# FINGER_USB_HUB.net
KiCad netlist of a schematic drawn in Altium Designer
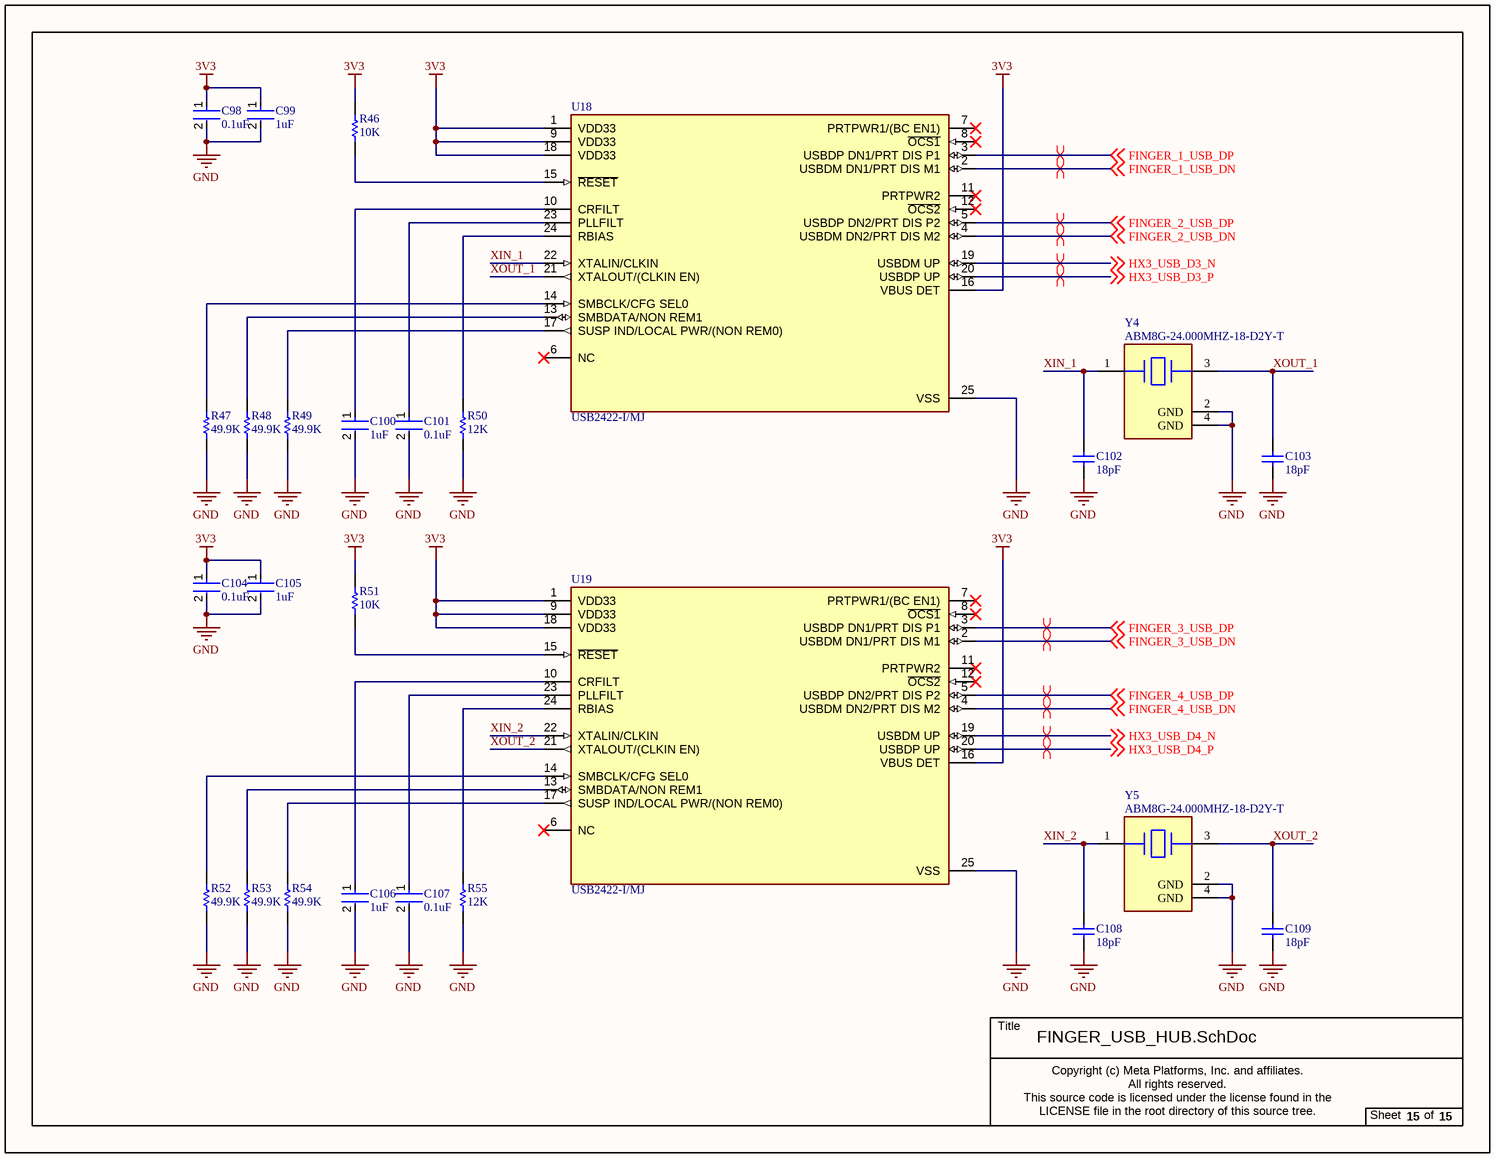
[diagram p0: FINGER_USB_HUB.SchDoc]

(export (version "E")
  (design (tool "Eeschema 10.0.6"))
  (components
    (comp (ref "C98")
      (value "0.1uF")
      (footprint "FP-CC0201-BA-MFG")
      (description "CAP CER 0.1UF 6.3V X5R 0201")
      (fields (field (name "MANUFACTURER") "Yageo") (field (name "TOLERANCE") "0.1"))
      (libsource (lib "Altium Content Vault") (part "11868f565c42a9108669ba33697ecf6"))
    )
    (comp (ref "C99")
      (value "1uF")
      (footprint "FP-CL511-IPC_C")
      (description "Cap Ceramic 1uF 10V X5R ±10% SMD 0402 +85°C Paper T/R")
      (fields (field (name "TOLERANCE") "10%"))
      (libsource (lib "Altium Content Vault") (part "b4654b650e69147ec39a6b967a45e02"))
    )
    (comp (ref "C100")
      (value "1uF")
      (footprint "FP-CL511-IPC_C")
      (description "Cap Ceramic 1uF 10V X5R ±10% SMD 0402 +85°C Paper T/R")
      (fields (field (name "TOLERANCE") "10%"))
      (libsource (lib "Altium Content Vault") (part "b4654b650e69147ec39a6b967a45e02"))
    )
    (comp (ref "C101")
      (value "0.1uF")
      (footprint "FP-CC0201-BA-MFG")
      (description "CAP CER 0.1UF 6.3V X5R 0201")
      (fields (field (name "MANUFACTURER") "Yageo") (field (name "TOLERANCE") "0.1"))
      (libsource (lib "Altium Content Vault") (part "11868f565c42a9108669ba33697ecf6"))
    )
    (comp (ref "C102")
      (value "18pF")
      (footprint "CAPC1005X55X25NL05T10")
      (fields (field (name "PART NUMBER") "GRM1555C1H180JA01D") (field (name "MANUFACTURER") "Murata"))
      (libsource (lib "Altium Content Vault") (part "CAP"))
    )
    (comp (ref "C103")
      (value "18pF")
      (footprint "CAPC1005X55X25NL05T10")
      (fields (field (name "PART NUMBER") "GRM1555C1H180JA01D") (field (name "MANUFACTURER") "Murata"))
      (libsource (lib "Altium Content Vault") (part "CAP"))
    )
    (comp (ref "C104")
      (value "0.1uF")
      (footprint "FP-CC0201-BA-MFG")
      (description "CAP CER 0.1UF 6.3V X5R 0201")
      (fields (field (name "MANUFACTURER") "Yageo") (field (name "TOLERANCE") "0.1"))
      (libsource (lib "Altium Content Vault") (part "11868f565c42a9108669ba33697ecf6"))
    )
    (comp (ref "C105")
      (value "1uF")
      (footprint "FP-CL511-IPC_C")
      (description "Cap Ceramic 1uF 10V X5R ±10% SMD 0402 +85°C Paper T/R")
      (fields (field (name "TOLERANCE") "10%"))
      (libsource (lib "Altium Content Vault") (part "b4654b650e69147ec39a6b967a45e02"))
    )
    (comp (ref "C106")
      (value "1uF")
      (footprint "FP-CL511-IPC_C")
      (description "Cap Ceramic 1uF 10V X5R ±10% SMD 0402 +85°C Paper T/R")
      (fields (field (name "TOLERANCE") "10%"))
      (libsource (lib "Altium Content Vault") (part "b4654b650e69147ec39a6b967a45e02"))
    )
    (comp (ref "C107")
      (value "0.1uF")
      (footprint "FP-CC0201-BA-MFG")
      (description "CAP CER 0.1UF 6.3V X5R 0201")
      (fields (field (name "MANUFACTURER") "Yageo") (field (name "TOLERANCE") "0.1"))
      (libsource (lib "Altium Content Vault") (part "11868f565c42a9108669ba33697ecf6"))
    )
    (comp (ref "C108")
      (value "18pF")
      (footprint "CAPC1005X55X25NL05T10")
      (fields (field (name "PART NUMBER") "GRM1555C1H180JA01D") (field (name "MANUFACTURER") "Murata"))
      (libsource (lib "Altium Content Vault") (part "CAP"))
    )
    (comp (ref "C109")
      (value "18pF")
      (footprint "CAPC1005X55X25NL05T10")
      (fields (field (name "PART NUMBER") "GRM1555C1H180JA01D") (field (name "MANUFACTURER") "Murata"))
      (libsource (lib "Altium Content Vault") (part "CAP"))
    )
    (comp (ref "R46")
      (value "10K")
      (footprint "RESC1005X40X25ML05T10")
      (fields (field (name "PART NUMBER") "CRCW040210K0FKEDHP") (field (name "MANUFACTURER") "Vishay Dale"))
      (libsource (lib "Altium Content Vault") (part "RES"))
    )
    (comp (ref "R47")
      (value "49.9K")
      (footprint "RESC1005X40X25ML05T10")
      (fields (field (name "MANUFACTURER") "Yageo / Phycomp") (field (name "PART NUMBER") "RC0402FR-0749K9L"))
      (libsource (lib "Altium Content Vault") (part "RES"))
    )
    (comp (ref "R48")
      (value "49.9K")
      (footprint "RESC1005X40X25ML05T10")
      (fields (field (name "MANUFACTURER") "Yageo / Phycomp") (field (name "PART NUMBER") "RC0402FR-0749K9L"))
      (libsource (lib "Altium Content Vault") (part "RES"))
    )
    (comp (ref "R49")
      (value "49.9K")
      (footprint "RESC1005X40X25ML05T10")
      (fields (field (name "MANUFACTURER") "Yageo / Phycomp") (field (name "PART NUMBER") "RC0402FR-0749K9L"))
      (libsource (lib "Altium Content Vault") (part "RES"))
    )
    (comp (ref "R50")
      (value "12K")
      (footprint "RESC1005X40X25ML05T05")
      (description "Chip Resistor, 12 KOhm, +/- 1%, 0.1 W, -55 to 155 degC, 0402 (1005 Metric), RoHS, Tape and Reel")
      (fields (field (name "TOLERANCE") "1%") (field (name "PARTNUMBER") "ERJ-2RKF1202X"))
      (libsource (lib "Altium Content Vault") (part "RES-2"))
    )
    (comp (ref "R51")
      (value "10K")
      (footprint "RESC1005X40X25ML05T10")
      (fields (field (name "PART NUMBER") "CRCW040210K0FKEDHP") (field (name "MANUFACTURER") "Vishay Dale"))
      (libsource (lib "Altium Content Vault") (part "RES"))
    )
    (comp (ref "R52")
      (value "49.9K")
      (footprint "RESC1005X40X25ML05T10")
      (fields (field (name "MANUFACTURER") "Yageo / Phycomp") (field (name "PART NUMBER") "RC0402FR-0749K9L"))
      (libsource (lib "Altium Content Vault") (part "RES"))
    )
    (comp (ref "R53")
      (value "49.9K")
      (footprint "RESC1005X40X25ML05T10")
      (fields (field (name "MANUFACTURER") "Yageo / Phycomp") (field (name "PART NUMBER") "RC0402FR-0749K9L"))
      (libsource (lib "Altium Content Vault") (part "RES"))
    )
    (comp (ref "R54")
      (value "49.9K")
      (footprint "RESC1005X40X25ML05T10")
      (fields (field (name "MANUFACTURER") "Yageo / Phycomp") (field (name "PART NUMBER") "RC0402FR-0749K9L"))
      (libsource (lib "Altium Content Vault") (part "RES"))
    )
    (comp (ref "R55")
      (value "12K")
      (footprint "RESC1005X40X25ML05T05")
      (description "Chip Resistor, 12 KOhm, +/- 1%, 0.1 W, -55 to 155 degC, 0402 (1005 Metric), RoHS, Tape and Reel")
      (fields (field (name "TOLERANCE") "1%") (field (name "PARTNUMBER") "ERJ-2RKF1202X"))
      (libsource (lib "Altium Content Vault") (part "RES-2"))
    )
    (comp (ref "U18")
      (value "USB2422-I/MJ")
      (footprint "FP-24-S4QFN-4x4B-0_5P-MFG")
      (description "IC HUB CTLR USB 2.0 24QFN")
      (fields
        (field (name "MANUFACTURER") "Microchip")
        (field (name "OCTOPART") "https://octopart.com/usb2422-i%2Fmj-microchip-29030614")
      )
      (libsource (lib "Altium Content Vault") (part "e4aea346ed290c10a3dfb05f2f32753"))
    )
    (comp (ref "U19")
      (value "USB2422-I/MJ")
      (footprint "FP-24-S4QFN-4x4B-0_5P-MFG")
      (description "IC HUB CTLR USB 2.0 24QFN")
      (fields
        (field (name "MANUFACTURER") "Microchip")
        (field (name "OCTOPART") "https://octopart.com/usb2422-i%2Fmj-microchip-29030614")
      )
      (libsource (lib "Altium Content Vault") (part "e4aea346ed290c10a3dfb05f2f32753"))
    )
    (comp (ref "Y4")
      (value "ABM8G-24.000MHZ-18-D2Y-T")
      (footprint "FP-ABM8G-MFG")
      (description "Crystal 24MHz ±20ppm (Tol) ±30ppm (Stability) 18pF FUND 60Ω 4-Pin SMD T/R")
      (fields (field (name "TOLERANCE") "20ppm"))
      (libsource (lib "Altium Content Vault") (part "48e526d86b7f2615d98721063c72f49"))
    )
    (comp (ref "Y5")
      (value "ABM8G-24.000MHZ-18-D2Y-T")
      (footprint "FP-ABM8G-MFG")
      (description "Crystal 24MHz ±20ppm (Tol) ±30ppm (Stability) 18pF FUND 60Ω 4-Pin SMD T/R")
      (fields (field (name "TOLERANCE") "20ppm"))
      (libsource (lib "Altium Content Vault") (part "48e526d86b7f2615d98721063c72f49"))
    )
  )
  (nets
    (net (code "1") (name "/XIN_1") (class "Default")
      (node (ref "C102") (pin "2") (pinfunction "2_2") (pintype "passive"))
      (node (ref "U18") (pin "22") (pinfunction "XTALIN/CLKIN_22") (pintype "input"))
      (node (ref "Y4") (pin "1") (pinfunction "1_1") (pintype "passive"))
    )
    (net (code "2") (name "/XIN_2") (class "Default")
      (node (ref "C108") (pin "2") (pinfunction "2_2") (pintype "passive"))
      (node (ref "U19") (pin "22") (pinfunction "XTALIN/CLKIN_22") (pintype "input"))
      (node (ref "Y5") (pin "1") (pinfunction "1_1") (pintype "passive"))
    )
    (net (code "3") (name "/XOUT_1") (class "Default")
      (node (ref "C103") (pin "2") (pinfunction "2_2") (pintype "passive"))
      (node (ref "U18") (pin "21") (pinfunction "XTALOUT/(CLKIN_EN)_21") (pintype "output"))
      (node (ref "Y4") (pin "3") (pinfunction "3_3") (pintype "passive"))
    )
    (net (code "4") (name "/XOUT_2") (class "Default")
      (node (ref "C109") (pin "2") (pinfunction "2_2") (pintype "passive"))
      (node (ref "U19") (pin "21") (pinfunction "XTALOUT/(CLKIN_EN)_21") (pintype "output"))
      (node (ref "Y5") (pin "3") (pinfunction "3_3") (pintype "passive"))
    )
    (net (code "5") (name "3V3") (class "Default")
      (node (ref "C104") (pin "1") (pinfunction "1_1") (pintype "passive"))
      (node (ref "C105") (pin "1") (pinfunction "1_1") (pintype "passive"))
      (node (ref "C98") (pin "1") (pinfunction "1_1") (pintype "passive"))
      (node (ref "C99") (pin "1") (pinfunction "1_1") (pintype "passive"))
      (node (ref "R46") (pin "2") (pinfunction "2_2") (pintype "passive"))
      (node (ref "R51") (pin "2") (pinfunction "2_2") (pintype "passive"))
      (node (ref "U18") (pin "1") (pinfunction "VDD33_1") (pintype "power_in"))
      (node (ref "U18") (pin "16") (pinfunction "VBUS_DET_16") (pintype "power_in"))
      (node (ref "U18") (pin "18") (pinfunction "VDD33_18") (pintype "power_in"))
      (node (ref "U18") (pin "9") (pinfunction "VDD33_9") (pintype "power_in"))
      (node (ref "U19") (pin "1") (pinfunction "VDD33_1") (pintype "power_in"))
      (node (ref "U19") (pin "16") (pinfunction "VBUS_DET_16") (pintype "power_in"))
      (node (ref "U19") (pin "18") (pinfunction "VDD33_18") (pintype "power_in"))
      (node (ref "U19") (pin "9") (pinfunction "VDD33_9") (pintype "power_in"))
    )
    (net (code "6") (name "FINGER_1_USB_DN") (class "Default")
      (node (ref "U18") (pin "2") (pinfunction "USBDM_DN1/PRT_DIS_M1_2") (pintype "bidirectional"))
    )
    (net (code "7") (name "FINGER_1_USB_DP") (class "Default")
      (node (ref "U18") (pin "3") (pinfunction "USBDP_DN1/PRT_DIS_P1_3") (pintype "bidirectional"))
    )
    (net (code "8") (name "FINGER_2_USB_DN") (class "Default")
      (node (ref "U18") (pin "4") (pinfunction "USBDM_DN2/PRT_DIS_M2_4") (pintype "bidirectional"))
    )
    (net (code "9") (name "FINGER_2_USB_DP") (class "Default")
      (node (ref "U18") (pin "5") (pinfunction "USBDP_DN2/PRT_DIS_P2_5") (pintype "bidirectional"))
    )
    (net (code "10") (name "FINGER_3_USB_DN") (class "Default")
      (node (ref "U19") (pin "2") (pinfunction "USBDM_DN1/PRT_DIS_M1_2") (pintype "bidirectional"))
    )
    (net (code "11") (name "FINGER_3_USB_DP") (class "Default")
      (node (ref "U19") (pin "3") (pinfunction "USBDP_DN1/PRT_DIS_P1_3") (pintype "bidirectional"))
    )
    (net (code "12") (name "FINGER_4_USB_DN") (class "Default")
      (node (ref "U19") (pin "4") (pinfunction "USBDM_DN2/PRT_DIS_M2_4") (pintype "bidirectional"))
    )
    (net (code "13") (name "FINGER_4_USB_DP") (class "Default")
      (node (ref "U19") (pin "5") (pinfunction "USBDP_DN2/PRT_DIS_P2_5") (pintype "bidirectional"))
    )
    (net (code "14") (name "GND") (class "Default")
      (node (ref "C100") (pin "2") (pinfunction "2_2") (pintype "passive"))
      (node (ref "C101") (pin "2") (pinfunction "2_2") (pintype "passive"))
      (node (ref "C102") (pin "1") (pinfunction "1_1") (pintype "passive"))
      (node (ref "C103") (pin "1") (pinfunction "1_1") (pintype "passive"))
      (node (ref "C104") (pin "2") (pinfunction "2_2") (pintype "passive"))
      (node (ref "C105") (pin "2") (pinfunction "2_2") (pintype "passive"))
      (node (ref "C106") (pin "2") (pinfunction "2_2") (pintype "passive"))
      (node (ref "C107") (pin "2") (pinfunction "2_2") (pintype "passive"))
      (node (ref "C108") (pin "1") (pinfunction "1_1") (pintype "passive"))
      (node (ref "C109") (pin "1") (pinfunction "1_1") (pintype "passive"))
      (node (ref "C98") (pin "2") (pinfunction "2_2") (pintype "passive"))
      (node (ref "C99") (pin "2") (pinfunction "2_2") (pintype "passive"))
      (node (ref "R47") (pin "1") (pinfunction "1_1") (pintype "passive"))
      (node (ref "R48") (pin "1") (pinfunction "1_1") (pintype "passive"))
      (node (ref "R49") (pin "1") (pinfunction "1_1") (pintype "passive"))
      (node (ref "R50") (pin "1") (pinfunction "1_1") (pintype "passive"))
      (node (ref "R52") (pin "1") (pinfunction "1_1") (pintype "passive"))
      (node (ref "R53") (pin "1") (pinfunction "1_1") (pintype "passive"))
      (node (ref "R54") (pin "1") (pinfunction "1_1") (pintype "passive"))
      (node (ref "R55") (pin "1") (pinfunction "1_1") (pintype "passive"))
      (node (ref "U18") (pin "25") (pinfunction "VSS_25") (pintype "power_in"))
      (node (ref "U19") (pin "25") (pinfunction "VSS_25") (pintype "power_in"))
      (node (ref "Y4") (pin "2") (pinfunction "GND_2") (pintype "power_in"))
      (node (ref "Y4") (pin "4") (pinfunction "GND_4") (pintype "power_in"))
      (node (ref "Y5") (pin "2") (pinfunction "GND_2") (pintype "power_in"))
      (node (ref "Y5") (pin "4") (pinfunction "GND_4") (pintype "power_in"))
    )
    (net (code "15") (name "HX3_USB_D3_N") (class "Default")
      (node (ref "U18") (pin "19") (pinfunction "USBDM_UP_19") (pintype "bidirectional"))
    )
    (net (code "16") (name "HX3_USB_D3_P") (class "Default")
      (node (ref "U18") (pin "20") (pinfunction "USBDP_UP_20") (pintype "bidirectional"))
    )
    (net (code "17") (name "HX3_USB_D4_N") (class "Default")
      (node (ref "U19") (pin "19") (pinfunction "USBDM_UP_19") (pintype "bidirectional"))
    )
    (net (code "18") (name "HX3_USB_D4_P") (class "Default")
      (node (ref "U19") (pin "20") (pinfunction "USBDP_UP_20") (pintype "bidirectional"))
    )
    (net (code "19") (name "Net-(U18-CRFILT)") (class "Default")
      (node (ref "C100") (pin "1") (pinfunction "1_1") (pintype "passive"))
      (node (ref "U18") (pin "10") (pinfunction "CRFILT_10") (pintype "passive"))
    )
    (net (code "20") (name "Net-(U18-PLLFILT)") (class "Default")
      (node (ref "C101") (pin "1") (pinfunction "1_1") (pintype "passive"))
      (node (ref "U18") (pin "23") (pinfunction "PLLFILT_23") (pintype "passive"))
    )
    (net (code "21") (name "Net-(U18-RBIAS)") (class "Default")
      (node (ref "R50") (pin "2") (pinfunction "2_2") (pintype "passive"))
      (node (ref "U18") (pin "24") (pinfunction "RBIAS_24") (pintype "passive"))
    )
    (net (code "22") (name "Net-(U18-SMBCLK{slash}CFG_SEL0)") (class "Default")
      (node (ref "R47") (pin "2") (pinfunction "2_2") (pintype "passive"))
      (node (ref "U18") (pin "14") (pinfunction "SMBCLK/CFG_SEL0_14") (pintype "input"))
    )
    (net (code "23") (name "Net-(U18-SMBDATA{slash}NON_REM1)") (class "Default")
      (node (ref "R48") (pin "2") (pinfunction "2_2") (pintype "passive"))
      (node (ref "U18") (pin "13") (pinfunction "SMBDATA/NON_REM1_13") (pintype "bidirectional"))
    )
    (net (code "24") (name "Net-(U18-SUSP_IND{slash}LOCAL_PWR{slash}(NON_REM0))") (class "Default")
      (node (ref "R49") (pin "2") (pinfunction "2_2") (pintype "passive"))
      (node (ref "U18") (pin "17") (pinfunction "SUSP_IND/LOCAL_PWR/(NON_REM0)_17") (pintype "output"))
    )
    (net (code "25") (name "Net-(U18-~{RESET})") (class "Default")
      (node (ref "R46") (pin "1") (pinfunction "1_1") (pintype "passive"))
      (node (ref "U18") (pin "15") (pinfunction "~{RESET}_15") (pintype "input"))
    )
    (net (code "26") (name "Net-(U19-CRFILT)") (class "Default")
      (node (ref "C106") (pin "1") (pinfunction "1_1") (pintype "passive"))
      (node (ref "U19") (pin "10") (pinfunction "CRFILT_10") (pintype "passive"))
    )
    (net (code "27") (name "Net-(U19-PLLFILT)") (class "Default")
      (node (ref "C107") (pin "1") (pinfunction "1_1") (pintype "passive"))
      (node (ref "U19") (pin "23") (pinfunction "PLLFILT_23") (pintype "passive"))
    )
    (net (code "28") (name "Net-(U19-RBIAS)") (class "Default")
      (node (ref "R55") (pin "2") (pinfunction "2_2") (pintype "passive"))
      (node (ref "U19") (pin "24") (pinfunction "RBIAS_24") (pintype "passive"))
    )
    (net (code "29") (name "Net-(U19-SMBCLK{slash}CFG_SEL0)") (class "Default")
      (node (ref "R52") (pin "2") (pinfunction "2_2") (pintype "passive"))
      (node (ref "U19") (pin "14") (pinfunction "SMBCLK/CFG_SEL0_14") (pintype "input"))
    )
    (net (code "30") (name "Net-(U19-SMBDATA{slash}NON_REM1)") (class "Default")
      (node (ref "R53") (pin "2") (pinfunction "2_2") (pintype "passive"))
      (node (ref "U19") (pin "13") (pinfunction "SMBDATA/NON_REM1_13") (pintype "bidirectional"))
    )
    (net (code "31") (name "Net-(U19-SUSP_IND{slash}LOCAL_PWR{slash}(NON_REM0))") (class "Default")
      (node (ref "R54") (pin "2") (pinfunction "2_2") (pintype "passive"))
      (node (ref "U19") (pin "17") (pinfunction "SUSP_IND/LOCAL_PWR/(NON_REM0)_17") (pintype "output"))
    )
    (net (code "32") (name "Net-(U19-~{RESET})") (class "Default")
      (node (ref "R51") (pin "1") (pinfunction "1_1") (pintype "passive"))
      (node (ref "U19") (pin "15") (pinfunction "~{RESET}_15") (pintype "input"))
    )
    (net (code "33") (name "unconnected-(U18-NC-Pad6)") (class "Default")
      (node (ref "U18") (pin "6") (pinfunction "NC_6") (pintype "passive+no_connect"))
    )
    (net (code "34") (name "unconnected-(U18-PRTPWR1{slash}(BC_EN1)-Pad7)") (class "Default")
      (node (ref "U18") (pin "7") (pinfunction "PRTPWR1/(BC_EN1)_7") (pintype "power_in+no_connect"))
    )
    (net (code "35") (name "unconnected-(U18-PRTPWR2-Pad11)") (class "Default")
      (node (ref "U18") (pin "11") (pinfunction "PRTPWR2_11") (pintype "power_in+no_connect"))
    )
    (net (code "36") (name "unconnected-(U18-~{OCS1}-Pad8)") (class "Default")
      (node (ref "U18") (pin "8") (pinfunction "~{OCS1}_8") (pintype "input+no_connect"))
    )
    (net (code "37") (name "unconnected-(U18-~{OCS2}-Pad12)") (class "Default")
      (node (ref "U18") (pin "12") (pinfunction "~{OCS2}_12") (pintype "input+no_connect"))
    )
    (net (code "38") (name "unconnected-(U19-NC-Pad6)") (class "Default")
      (node (ref "U19") (pin "6") (pinfunction "NC_6") (pintype "passive+no_connect"))
    )
    (net (code "39") (name "unconnected-(U19-PRTPWR1{slash}(BC_EN1)-Pad7)") (class "Default")
      (node (ref "U19") (pin "7") (pinfunction "PRTPWR1/(BC_EN1)_7") (pintype "power_in+no_connect"))
    )
    (net (code "40") (name "unconnected-(U19-PRTPWR2-Pad11)") (class "Default")
      (node (ref "U19") (pin "11") (pinfunction "PRTPWR2_11") (pintype "power_in+no_connect"))
    )
    (net (code "41") (name "unconnected-(U19-~{OCS1}-Pad8)") (class "Default")
      (node (ref "U19") (pin "8") (pinfunction "~{OCS1}_8") (pintype "input+no_connect"))
    )
    (net (code "42") (name "unconnected-(U19-~{OCS2}-Pad12)") (class "Default")
      (node (ref "U19") (pin "12") (pinfunction "~{OCS2}_12") (pintype "input+no_connect"))
    )
  )
)
